# SCS_V2.net
KiCad netlist of a schematic drawn in EAGLE
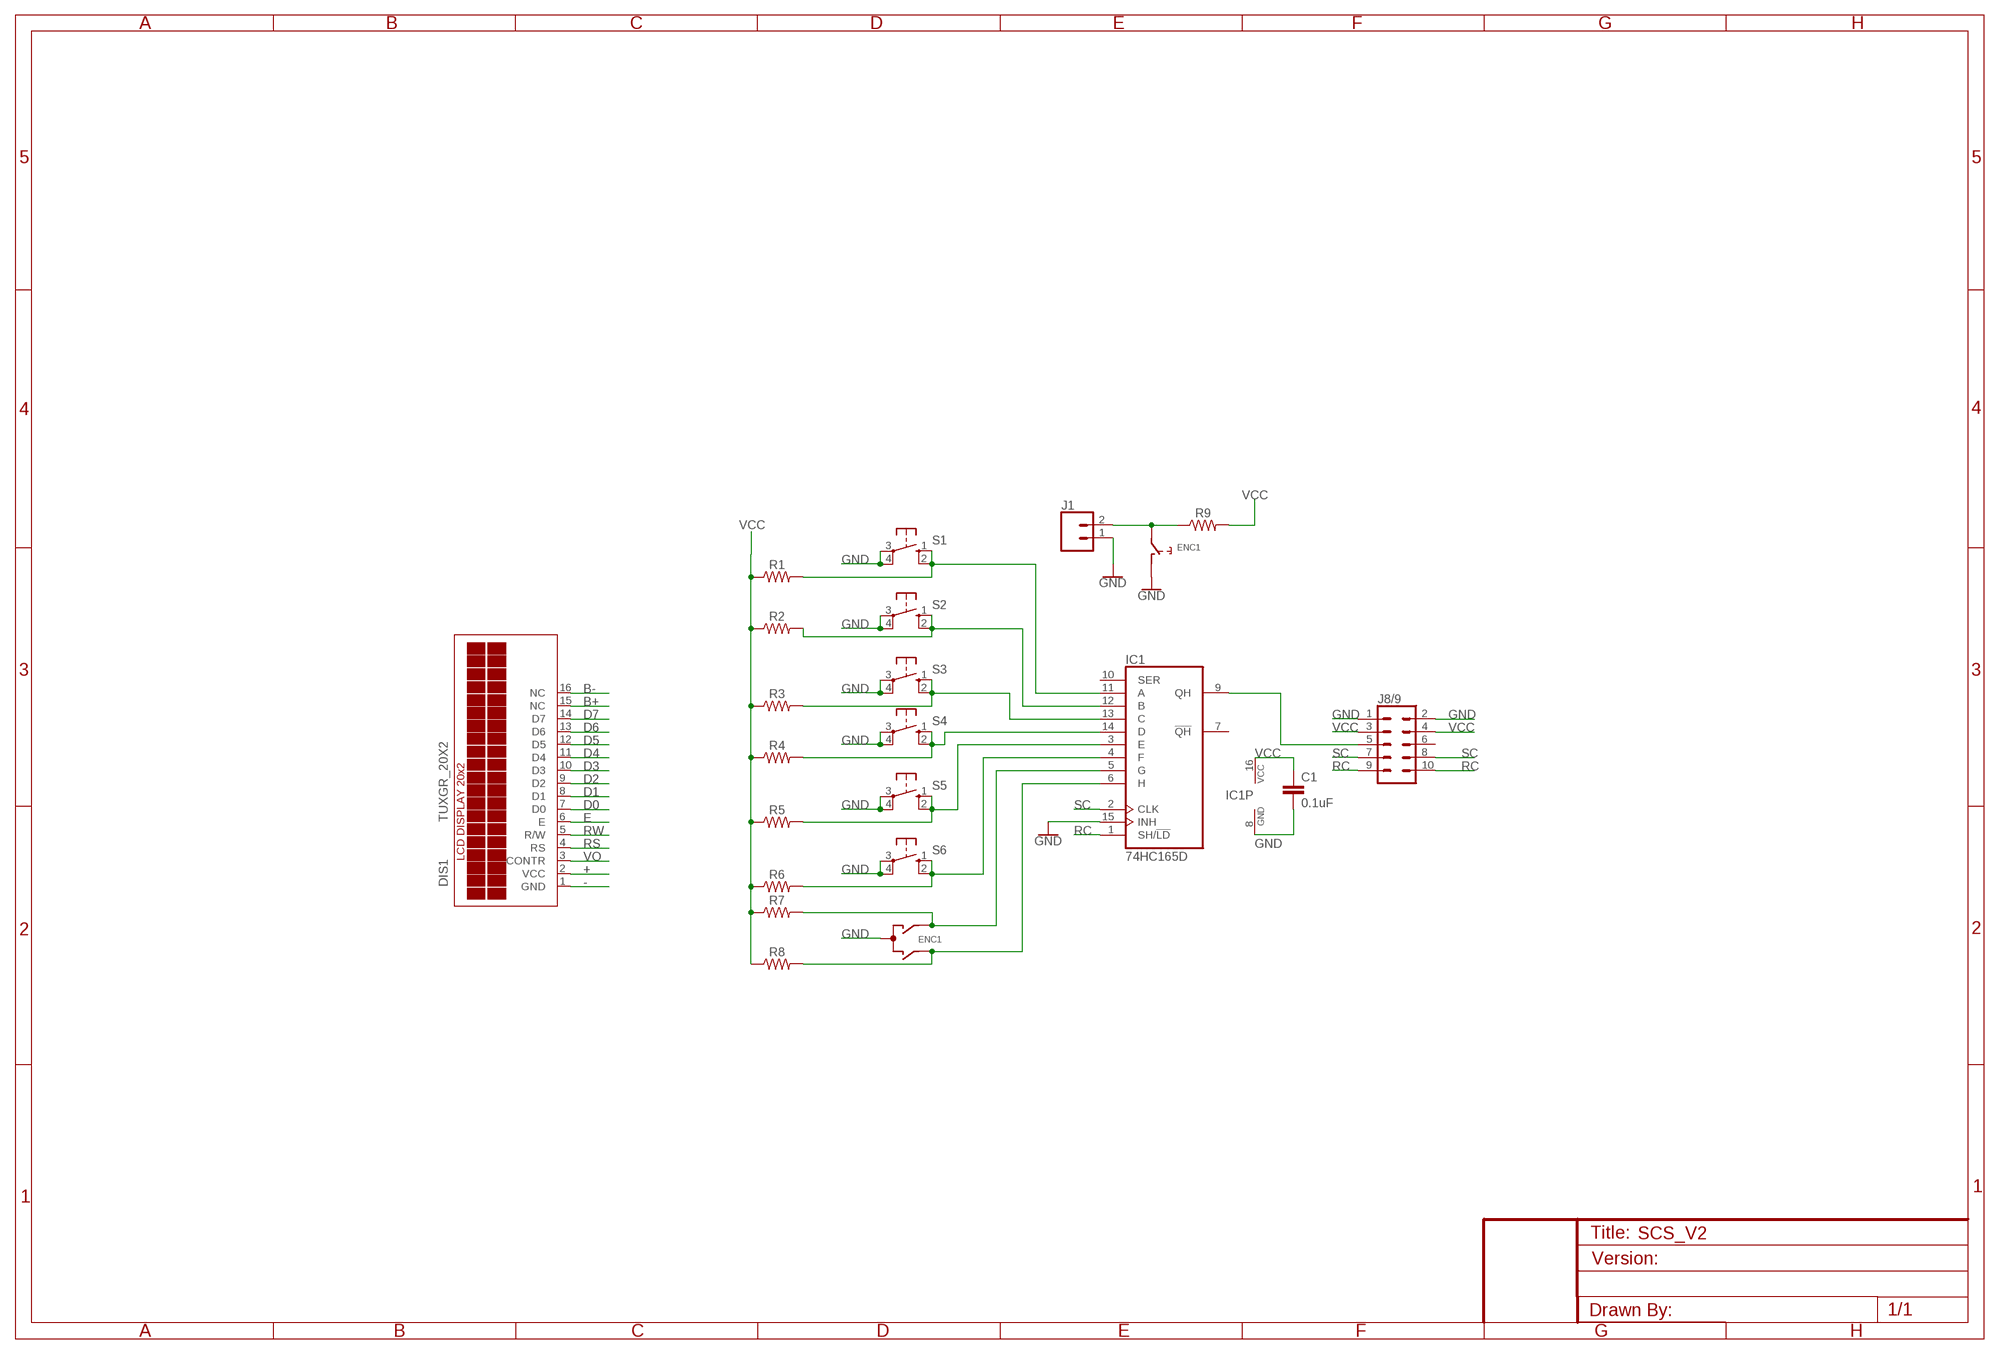
[diagram p0: schematic, sheet 1]

(export (version "E")
  (design (tool "Eeschema 10.0.6"))
  (components
    (comp (ref "C1")
      (value "0.1uF")
      (footprint "eagle-import:0603")
      (libsource (lib "eagle-import") (part "0.1UF-0603-25V-(+80/-20%)"))
    )
    (comp (ref "DIS1")
      (value "TUXGR_20X2")
      (footprint "eagle-import:TUXGR_20X2")
      (libsource (lib "eagle-import") (part "TUXGR_20X2"))
    )
    (comp (ref "ENC1")
      (value "EC12E_SW")
      (footprint "eagle-import:ALPS_EC12E_SW")
      (fields (field (name "MPN") "EC12E2424407"))
      (libsource (lib "eagle-import") (part "EC12E_SW"))
    )
    (comp (ref "IC1")
      (value "74HC165D")
      (footprint "eagle-import:SO16")
      (libsource (lib "eagle-import") (part "74165DHC"))
    )
    (comp (ref "J1")
      (value "CONN_02")
      (footprint "eagle-import:1X02")
      (libsource (lib "eagle-import") (part "CONN_02"))
    )
    (comp (ref "J8/9")
      (value "CONN_05X2SHD_LOCK")
      (footprint "eagle-import:2X5-SHROUDED_LOCK")
      (libsource (lib "eagle-import") (part "CONN_05X2SHD_LOCK"))
    )
    (comp (ref "R1")
      (value "10k")
      (footprint "eagle-import:0603")
      (libsource (lib "eagle-import") (part "10KOHM-0603-1/10W-1%"))
    )
    (comp (ref "R2")
      (value "10k")
      (footprint "eagle-import:0603")
      (libsource (lib "eagle-import") (part "10KOHM-0603-1/10W-1%"))
    )
    (comp (ref "R3")
      (value "10k")
      (footprint "eagle-import:0603")
      (libsource (lib "eagle-import") (part "10KOHM-0603-1/10W-1%"))
    )
    (comp (ref "R4")
      (value "10k")
      (footprint "eagle-import:0603")
      (libsource (lib "eagle-import") (part "10KOHM-0603-1/10W-1%"))
    )
    (comp (ref "R5")
      (value "10k")
      (footprint "eagle-import:0603")
      (libsource (lib "eagle-import") (part "10KOHM-0603-1/10W-1%"))
    )
    (comp (ref "R6")
      (value "10k")
      (footprint "eagle-import:0603")
      (libsource (lib "eagle-import") (part "10KOHM-0603-1/10W-1%"))
    )
    (comp (ref "R7")
      (value "10k")
      (footprint "eagle-import:0603")
      (libsource (lib "eagle-import") (part "10KOHM-0603-1/10W-1%"))
    )
    (comp (ref "R8")
      (value "10k")
      (footprint "eagle-import:0603")
      (libsource (lib "eagle-import") (part "10KOHM-0603-1/10W-1%"))
    )
    (comp (ref "R9")
      (value "10k")
      (footprint "eagle-import:0603")
      (libsource (lib "eagle-import") (part "10KOHM-0603-1/10W-1%"))
    )
    (comp (ref "S1")
      (value "40-XX")
      (footprint "eagle-import:B3F-40XX")
      (fields (field (name "MF") "OMRON COMPONENTS USA") (field (name "MPN") "B3F-4000"))
      (libsource (lib "eagle-import") (part "40-XX"))
    )
    (comp (ref "S2")
      (value "40-XX")
      (footprint "eagle-import:B3F-40XX")
      (fields (field (name "MF") "OMRON COMPONENTS USA") (field (name "MPN") "B3F-4000"))
      (libsource (lib "eagle-import") (part "40-XX"))
    )
    (comp (ref "S3")
      (value "40-XX")
      (footprint "eagle-import:B3F-40XX")
      (fields (field (name "MF") "OMRON COMPONENTS USA") (field (name "MPN") "B3F-4000"))
      (libsource (lib "eagle-import") (part "40-XX"))
    )
    (comp (ref "S4")
      (value "40-XX")
      (footprint "eagle-import:B3F-40XX")
      (fields (field (name "MF") "OMRON COMPONENTS USA") (field (name "MPN") "B3F-4000"))
      (libsource (lib "eagle-import") (part "40-XX"))
    )
    (comp (ref "S5")
      (value "40-XX")
      (footprint "eagle-import:B3F-40XX")
      (fields (field (name "MF") "OMRON COMPONENTS USA") (field (name "MPN") "B3F-4000"))
      (libsource (lib "eagle-import") (part "40-XX"))
    )
    (comp (ref "S6")
      (value "40-XX")
      (footprint "eagle-import:B3F-40XX")
      (fields (field (name "MF") "OMRON COMPONENTS USA") (field (name "MPN") "B3F-4000"))
      (libsource (lib "eagle-import") (part "40-XX"))
    )
  )
  (nets
    (net (code "1") (name "/+") (class "Default")
      (node (ref "DIS1") (pin "2") (pinfunction "VCC_2") (pintype "power_in"))
    )
    (net (code "2") (name "/-") (class "Default")
      (node (ref "DIS1") (pin "1") (pinfunction "GND_1") (pintype "power_in"))
    )
    (net (code "5") (name "/D0") (class "Default")
      (node (ref "DIS1") (pin "7") (pinfunction "D0_7") (pintype "input"))
    )
    (net (code "6") (name "/D1") (class "Default")
      (node (ref "DIS1") (pin "8") (pinfunction "D1_8") (pintype "input"))
    )
    (net (code "7") (name "/D2") (class "Default")
      (node (ref "DIS1") (pin "9") (pinfunction "D2_9") (pintype "input"))
    )
    (net (code "8") (name "/D3") (class "Default")
      (node (ref "DIS1") (pin "10") (pinfunction "D3_10") (pintype "input"))
    )
    (net (code "9") (name "/D4") (class "Default")
      (node (ref "DIS1") (pin "11") (pinfunction "D4_11") (pintype "input"))
    )
    (net (code "10") (name "/D5") (class "Default")
      (node (ref "DIS1") (pin "12") (pinfunction "D5_12") (pintype "input"))
    )
    (net (code "11") (name "/D6") (class "Default")
      (node (ref "DIS1") (pin "13") (pinfunction "D6_13") (pintype "input"))
    )
    (net (code "12") (name "/D7") (class "Default")
      (node (ref "DIS1") (pin "14") (pinfunction "D7_14") (pintype "input"))
    )
    (net (code "13") (name "/E") (class "Default")
      (node (ref "DIS1") (pin "6") (pinfunction "E_6") (pintype "input"))
    )
    (net (code "14") (name "/RC") (class "Default")
      (node (ref "IC1") (pin "1") (pinfunction "SH/~{LD}_1") (pintype "input"))
      (node (ref "J8/9") (pin "10") (pinfunction "10_10") (pintype "passive"))
      (node (ref "J8/9") (pin "9") (pinfunction "9_9") (pintype "passive"))
    )
    (net (code "15") (name "/RS") (class "Default")
      (node (ref "DIS1") (pin "4") (pinfunction "RS_4") (pintype "input"))
    )
    (net (code "16") (name "/RW") (class "Default")
      (node (ref "DIS1") (pin "5") (pinfunction "R/W_5") (pintype "input"))
    )
    (net (code "17") (name "/SC") (class "Default")
      (node (ref "IC1") (pin "2") (pinfunction "CLK_2") (pintype "input"))
      (node (ref "J8/9") (pin "7") (pinfunction "7_7") (pintype "passive"))
      (node (ref "J8/9") (pin "8") (pinfunction "8_8") (pintype "passive"))
    )
    (net (code "18") (name "/VCC") (class "Default")
      (node (ref "C1") (pin "1") (pinfunction "1_1") (pintype "passive"))
      (node (ref "IC1") (pin "16") (pinfunction "VCC_16") (pintype "power_in"))
      (node (ref "J8/9") (pin "3") (pinfunction "3_3") (pintype "passive"))
      (node (ref "J8/9") (pin "4") (pinfunction "4_4") (pintype "passive"))
      (node (ref "R1") (pin "1") (pinfunction "1_1") (pintype "passive"))
      (node (ref "R2") (pin "1") (pinfunction "1_1") (pintype "passive"))
      (node (ref "R3") (pin "1") (pinfunction "1_1") (pintype "passive"))
      (node (ref "R4") (pin "1") (pinfunction "1_1") (pintype "passive"))
      (node (ref "R5") (pin "1") (pinfunction "1_1") (pintype "passive"))
      (node (ref "R6") (pin "1") (pinfunction "1_1") (pintype "passive"))
      (node (ref "R7") (pin "1") (pinfunction "1_1") (pintype "passive"))
      (node (ref "R8") (pin "1") (pinfunction "1_1") (pintype "passive"))
      (node (ref "R9") (pin "2") (pinfunction "2_2") (pintype "passive"))
    )
    (net (code "19") (name "/VO") (class "Default")
      (node (ref "DIS1") (pin "3") (pinfunction "CONTR_3") (pintype "input"))
    )
    (net (code "20") (name "GND") (class "Default")
      (node (ref "C1") (pin "2") (pinfunction "2_2") (pintype "passive"))
      (node (ref "ENC1") (pin "C") (pinfunction "C_C") (pintype "passive"))
      (node (ref "ENC1") (pin "D") (pinfunction "1_D") (pintype "passive"))
      (node (ref "IC1") (pin "15") (pinfunction "INH_15") (pintype "input"))
      (node (ref "IC1") (pin "8") (pinfunction "GND_8") (pintype "power_in"))
      (node (ref "J1") (pin "1") (pinfunction "1_1") (pintype "passive"))
      (node (ref "J8/9") (pin "1") (pinfunction "1_1") (pintype "passive"))
      (node (ref "J8/9") (pin "2") (pinfunction "2_2") (pintype "passive"))
      (node (ref "S1") (pin "3") (pinfunction "P_3") (pintype "passive"))
      (node (ref "S1") (pin "4") (pinfunction "P1_4") (pintype "passive"))
      (node (ref "S2") (pin "3") (pinfunction "P_3") (pintype "passive"))
      (node (ref "S2") (pin "4") (pinfunction "P1_4") (pintype "passive"))
      (node (ref "S3") (pin "3") (pinfunction "P_3") (pintype "passive"))
      (node (ref "S3") (pin "4") (pinfunction "P1_4") (pintype "passive"))
      (node (ref "S4") (pin "3") (pinfunction "P_3") (pintype "passive"))
      (node (ref "S4") (pin "4") (pinfunction "P1_4") (pintype "passive"))
      (node (ref "S5") (pin "3") (pinfunction "P_3") (pintype "passive"))
      (node (ref "S5") (pin "4") (pinfunction "P1_4") (pintype "passive"))
      (node (ref "S6") (pin "3") (pinfunction "P_3") (pintype "passive"))
      (node (ref "S6") (pin "4") (pinfunction "P1_4") (pintype "passive"))
    )
    (net (code "21") (name "Net-(ENC1B-2)") (class "Default")
      (node (ref "ENC1") (pin "E") (pinfunction "2_E") (pintype "passive"))
      (node (ref "J1") (pin "2") (pinfunction "2_2") (pintype "passive"))
      (node (ref "R9") (pin "1") (pinfunction "1_1") (pintype "passive"))
    )
    (net (code "22") (name "Net-(IC1A-A)") (class "Default")
      (node (ref "IC1") (pin "11") (pinfunction "A_11") (pintype "input"))
      (node (ref "R1") (pin "2") (pinfunction "2_2") (pintype "passive"))
      (node (ref "S1") (pin "1") (pinfunction "S_1") (pintype "passive"))
      (node (ref "S1") (pin "2") (pinfunction "S1_2") (pintype "passive"))
    )
    (net (code "23") (name "Net-(IC1A-B)") (class "Default")
      (node (ref "IC1") (pin "12") (pinfunction "B_12") (pintype "input"))
      (node (ref "R2") (pin "2") (pinfunction "2_2") (pintype "passive"))
      (node (ref "S2") (pin "1") (pinfunction "S_1") (pintype "passive"))
      (node (ref "S2") (pin "2") (pinfunction "S1_2") (pintype "passive"))
    )
    (net (code "24") (name "Net-(IC1A-C)") (class "Default")
      (node (ref "IC1") (pin "13") (pinfunction "C_13") (pintype "input"))
      (node (ref "R3") (pin "2") (pinfunction "2_2") (pintype "passive"))
      (node (ref "S3") (pin "1") (pinfunction "S_1") (pintype "passive"))
      (node (ref "S3") (pin "2") (pinfunction "S1_2") (pintype "passive"))
    )
    (net (code "25") (name "Net-(IC1A-D)") (class "Default")
      (node (ref "IC1") (pin "14") (pinfunction "D_14") (pintype "input"))
      (node (ref "R4") (pin "2") (pinfunction "2_2") (pintype "passive"))
      (node (ref "S4") (pin "1") (pinfunction "S_1") (pintype "passive"))
      (node (ref "S4") (pin "2") (pinfunction "S1_2") (pintype "passive"))
    )
    (net (code "26") (name "Net-(IC1A-E)") (class "Default")
      (node (ref "IC1") (pin "3") (pinfunction "E_3") (pintype "input"))
      (node (ref "R5") (pin "2") (pinfunction "2_2") (pintype "passive"))
      (node (ref "S5") (pin "1") (pinfunction "S_1") (pintype "passive"))
      (node (ref "S5") (pin "2") (pinfunction "S1_2") (pintype "passive"))
    )
    (net (code "27") (name "Net-(IC1A-F)") (class "Default")
      (node (ref "IC1") (pin "4") (pinfunction "F_4") (pintype "input"))
      (node (ref "R6") (pin "2") (pinfunction "2_2") (pintype "passive"))
      (node (ref "S6") (pin "1") (pinfunction "S_1") (pintype "passive"))
      (node (ref "S6") (pin "2") (pinfunction "S1_2") (pintype "passive"))
    )
    (net (code "28") (name "Net-(IC1A-G)") (class "Default")
      (node (ref "ENC1") (pin "A") (pinfunction "A_A") (pintype "passive"))
      (node (ref "IC1") (pin "5") (pinfunction "G_5") (pintype "input"))
      (node (ref "R7") (pin "2") (pinfunction "2_2") (pintype "passive"))
    )
    (net (code "29") (name "Net-(IC1A-H)") (class "Default")
      (node (ref "ENC1") (pin "B") (pinfunction "B_B") (pintype "passive"))
      (node (ref "IC1") (pin "6") (pinfunction "H_6") (pintype "input"))
      (node (ref "R8") (pin "2") (pinfunction "2_2") (pintype "passive"))
    )
    (net (code "30") (name "Net-(IC1A-QH)") (class "Default")
      (node (ref "IC1") (pin "9") (pinfunction "QH_9") (pintype "output"))
      (node (ref "J8/9") (pin "5") (pinfunction "5_5") (pintype "passive"))
    )
    (net (code "31") (name "unconnected-(DIS1-NC-Pad15)") (class "Default")
      (node (ref "DIS1") (pin "15") (pinfunction "NC_15") (pintype "no_connect"))
    )
    (net (code "32") (name "unconnected-(DIS1-NC-Pad16)") (class "Default")
      (node (ref "DIS1") (pin "16") (pinfunction "NC_16") (pintype "no_connect"))
    )
    (net (code "33") (name "unconnected-(IC1A-SER-Pad10)") (class "Default")
      (node (ref "IC1") (pin "10") (pinfunction "SER_10") (pintype "input"))
    )
    (net (code "34") (name "unconnected-(IC1A-~{QH}-Pad7)") (class "Default")
      (node (ref "IC1") (pin "7") (pinfunction "~{QH}_7") (pintype "output"))
    )
    (net (code "35") (name "unconnected-(J8/9-Pad6)") (class "Default")
      (node (ref "J8/9") (pin "6") (pinfunction "6_6") (pintype "passive"))
    )
  )
)
